# Power.net
KiCad netlist of a schematic drawn in Altium Designer
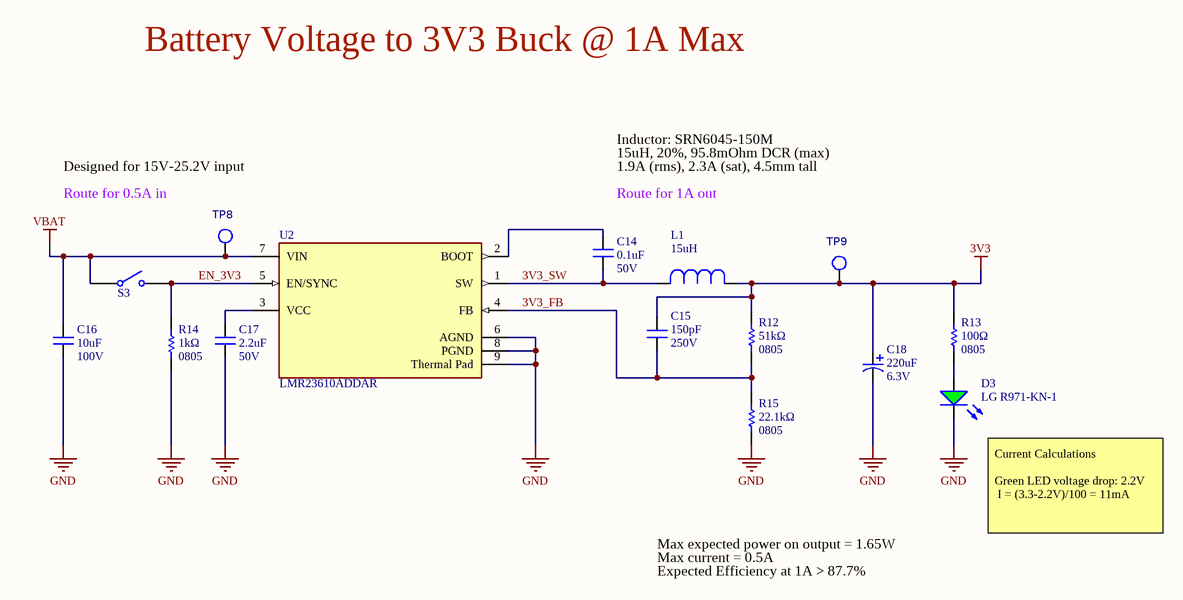
[diagram p0: Power.SchDoc]

(export (version "E")
  (design (tool "Eeschema 10.0.6"))
  (components
    (comp (ref "C14")
      (value "0.1uF")
      (footprint "CAPC2012X140N")
      (description "CAP CER 0.1UF 50V X7R 0805")
      (fields
        (field (name "TOLERANCE") "10%")
        (field (name "VOLTAGE RATING") "50V")
        (field (name "Comment") "CAP_0.1uF_50V_0805")
      )
      (libsource (lib "UWRT_Schematic_Library_2020") (part "CAP_0.1uF_50V_0805"))
    )
    (comp (ref "C15")
      (value "150pF")
      (footprint "CAPC2012X140N")
      (description "CAP CER 150PF 250V C0G/NP0 0805")
      (fields
        (field (name "TOLERANCE") "5%")
        (field (name "VOLTAGE RATING") "250V")
        (field (name "Comment") "CAP_150pF_250V_0805")
      )
      (libsource (lib "UWRT_Schematic_Library_2020") (part "CAP_150pF_250V_0805"))
    )
    (comp (ref "C16")
      (value "10uF")
      (footprint "CAPC1210(3225)")
      (description "CAP CER 10UF 100V X7S 1210")
      (fields (field (name "VOLTAGE RATING") "100V") (field (name "Comment") "CAP_10uF_100V_1210"))
      (libsource (lib "UWRT_Schematic_Library_2020") (part "CAP_10uF_100V_1210"))
    )
    (comp (ref "C17")
      (value "2.2uF")
      (footprint "CAPC1206(3216)")
      (description "CAP CER 2.2UF 50V X7R 1206")
      (fields
        (field (name "TOLERANCE") "10%")
        (field (name "VOLTAGE") "50V")
        (field (name "VOLTAGE RATING") "50V")
      )
      (libsource (lib "UWRT_Schematic_Library_2020") (part "CAP_2.2uF_50V_1206"))
    )
    (comp (ref "C18")
      (value "220uF")
      (footprint "PCAP_SVP_B6_PA00")
      (description "CAP ALUM POLY 220UF 20% 6.3V SMD")
      (fields (field (name "VOLTAGE RATING") "6.3V") (field (name "Comment") "CAP_220uF_6.3V_SMD"))
      (libsource (lib "UWRT_Schematic_Library_2020") (part "CAP_220uF_6.3V_SMD"))
    )
    (comp (ref "D3")
      (value "DIO_LED_G")
      (footprint "LED_0805_LINE")
      (description "LED GREEN DIFFUSED 0805 SMD")
      (fields (field (name "MANUFACTURER PART NUMBER 1") "LG R971-KN-1"))
      (libsource (lib "UWRT_Schematic_Library_2020") (part "DIO_LED_G"))
    )
    (comp (ref "L1")
      (value "SRN6045-150M")
      (footprint "IND_BOURNS_SRN6045")
      (description "FIXED IND 15UH 1.9A 95.8MOHM SMD")
      (fields (field (name "TOLERANCE") "20%") (field (name "INDUCTANCE") "15uH"))
      (libsource (lib "UWRT_Schematic_Library_2020") (part "IND_15uH_1.9A"))
    )
    (comp (ref "R12")
      (value "51kΩ")
      (footprint "RESC2012X60N")
      (description "RES SMD 51K OHM 1% 1/8W 0805")
      (fields
        (field (name "CASE CODE (IMPERIAL)") "0805")
        (field (name "TOLERANCE") "1%")
        (field (name "Comment") "RES_51kΩ_0805")
      )
      (libsource (lib "UWRT_Schematic_Library_2020") (part "RES_51kΩ_0805"))
    )
    (comp (ref "R13")
      (value "100Ω")
      (footprint "RESC2012X60N")
      (description "RES SMD 100 OHM 1% 1/8W 0805")
      (fields (field (name "CASE CODE (IMPERIAL)") "0805") (field (name "Comment") "RES_100Ω_0805"))
      (libsource (lib "UWRT_Schematic_Library_2020") (part "RES_100Ω_0805"))
    )
    (comp (ref "R14")
      (value "1kΩ")
      (footprint "RESC2012X60N")
      (description "RES SMD 1K OHM 1% 1/8W 0805")
      (fields
        (field (name "CASE CODE (IMPERIAL)") "0805")
        (field (name "TOLERANCE") "1%")
        (field (name "Comment") "RES_1kΩ_0805")
      )
      (libsource (lib "UWRT_Schematic_Library_2020") (part "RES_1kΩ_0805"))
    )
    (comp (ref "R15")
      (value "RES_22.1kΩ_0805")
      (footprint "RESC2012X60N")
      (description "RES SMD 22.1K OHM 1% 1/8W 0805")
      (fields
        (field (name "CASE CODE (IMPERIAL)") "0805")
        (field (name "RESISTANCE") "22.1kΩ")
        (field (name "TOLERANCE") "1%")
      )
      (libsource (lib "UWRT_Schematic_Library_2020") (part "RES_22.1kΩ_0805"))
    )
    (comp (ref "S3")
      (value "GF-123-0054")
      (footprint "GF1230054")
      (description "SWITCH SLIDE SPST 500mA (DC) 8.5A (AC) 125V")
      (libsource (lib "UWRT_Schematic_Library_2020") (part "GF-123-0054"))
    )
    (comp (ref "TP8")
      (value "TESTPOINT_LOOP")
      (footprint "TESTPOINT_LOOP")
      (description "Loop testpoint through-hole pad")
      (libsource (lib "UWRT_Schematic_Library_2020") (part "TESTPOINT_LOOP"))
    )
    (comp (ref "TP9")
      (value "TESTPOINT_LOOP")
      (footprint "TESTPOINT_LOOP")
      (description "Loop testpoint through-hole pad")
      (libsource (lib "UWRT_Schematic_Library_2020") (part "TESTPOINT_LOOP"))
    )
    (comp (ref "U2")
      (value "LMR23610ADDAR")
      (footprint "8-SO PowerPad")
      (description "IC REG BUCK ADJUSTABLE 1A 8SOPWR")
      (fields (field (name "OCTOPART") "https://octopart.com/lmr23610addar-texas+instruments-68058948"))
      (libsource (lib "UWRT_Schematic_Library_2020") (part "BUCK_1-28VOUT_1A"))
    )
  )
  (nets
    (net (code "1") (name "/3V3_FB") (class "Default")
      (node (ref "C15") (pin "2") (pinfunction "2_2") (pintype "passive"))
      (node (ref "R12") (pin "1") (pinfunction "1_1") (pintype "passive"))
      (node (ref "R15") (pin "2") (pinfunction "2_2") (pintype "passive"))
      (node (ref "U2") (pin "4") (pinfunction "FB_4") (pintype "input"))
    )
    (net (code "2") (name "/3V3_SW") (class "Default")
      (node (ref "C14") (pin "1") (pinfunction "1_1") (pintype "passive"))
      (node (ref "L1") (pin "2") (pinfunction "2_2") (pintype "passive"))
      (node (ref "U2") (pin "1") (pinfunction "SW_1") (pintype "output"))
    )
    (net (code "3") (name "/EN_3V3") (class "Default")
      (node (ref "R14") (pin "2") (pinfunction "2_2") (pintype "passive"))
      (node (ref "S3") (pin "2") (pintype "passive"))
      (node (ref "U2") (pin "5") (pinfunction "EN/SYNC_5") (pintype "input"))
    )
    (net (code "4") (name "3V3") (class "Default")
      (node (ref "C15") (pin "1") (pinfunction "1_1") (pintype "passive"))
      (node (ref "C18") (pin "1") (pinfunction "1_1") (pintype "passive"))
      (node (ref "L1") (pin "1") (pinfunction "1_1") (pintype "passive"))
      (node (ref "R12") (pin "2") (pinfunction "2_2") (pintype "passive"))
      (node (ref "R13") (pin "2") (pinfunction "2_2") (pintype "passive"))
      (node (ref "TP9") (pin "1") (pintype "passive"))
    )
    (net (code "5") (name "GND") (class "Default")
      (node (ref "C16") (pin "1") (pinfunction "1_1") (pintype "passive"))
      (node (ref "C17") (pin "1") (pinfunction "1_1") (pintype "passive"))
      (node (ref "C18") (pin "2") (pinfunction "2_2") (pintype "passive"))
      (node (ref "D3") (pin "2") (pinfunction "K_2") (pintype "passive"))
      (node (ref "R14") (pin "1") (pinfunction "1_1") (pintype "passive"))
      (node (ref "R15") (pin "1") (pinfunction "1_1") (pintype "passive"))
      (node (ref "U2") (pin "6") (pinfunction "AGND_6") (pintype "power_in"))
      (node (ref "U2") (pin "8") (pinfunction "PGND_8") (pintype "power_in"))
      (node (ref "U2") (pin "9") (pinfunction "Thermal_Pad_9") (pintype "power_in"))
    )
    (net (code "6") (name "Net-(D3-A)") (class "Default")
      (node (ref "D3") (pin "1") (pinfunction "A_1") (pintype "passive"))
      (node (ref "R13") (pin "1") (pinfunction "1_1") (pintype "passive"))
    )
    (net (code "7") (name "Net-(U2-BOOT)") (class "Default")
      (node (ref "C14") (pin "2") (pinfunction "2_2") (pintype "passive"))
      (node (ref "U2") (pin "2") (pinfunction "BOOT_2") (pintype "output"))
    )
    (net (code "8") (name "Net-(U2-VCC)") (class "Default")
      (node (ref "C17") (pin "2") (pinfunction "2_2") (pintype "passive"))
      (node (ref "U2") (pin "3") (pinfunction "VCC_3") (pintype "power_in"))
    )
    (net (code "9") (name "VBAT") (class "Default")
      (node (ref "C16") (pin "2") (pinfunction "2_2") (pintype "passive"))
      (node (ref "S3") (pin "1") (pintype "passive"))
      (node (ref "TP8") (pin "1") (pintype "passive"))
      (node (ref "U2") (pin "7") (pinfunction "VIN_7") (pintype "power_in"))
    )
  )
)
